# JHDrivesheet1.net
KiCad netlist of a schematic drawn in Altium Designer
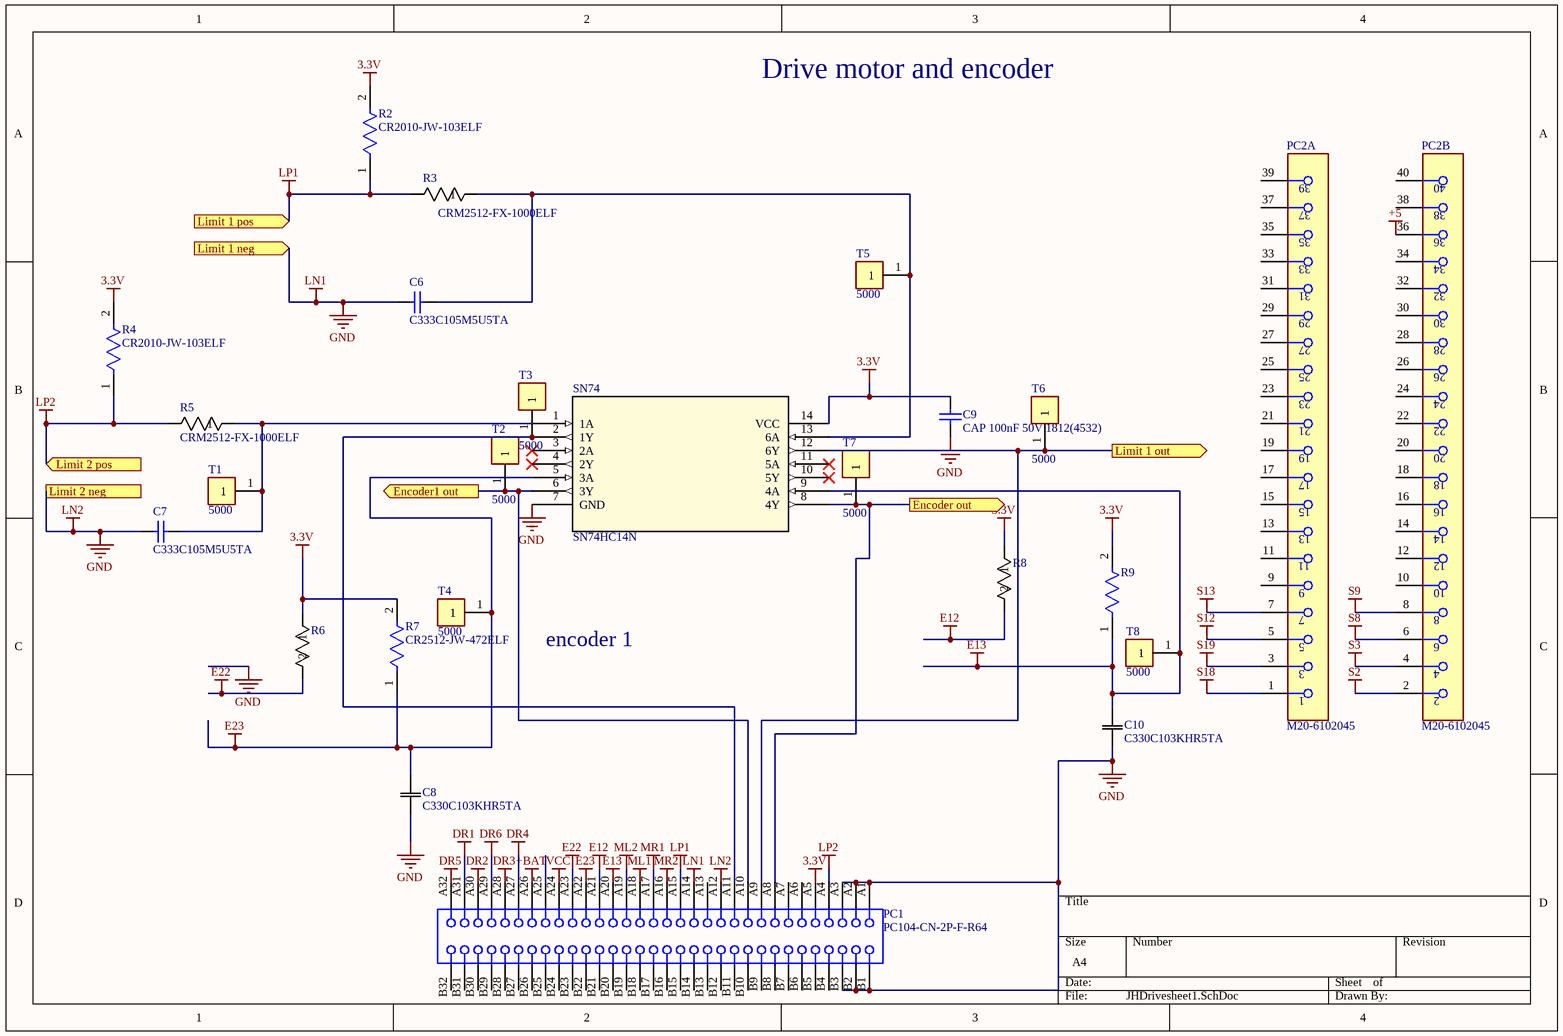
[diagram p0: JHDrivesheet1.SchDoc]

(export (version "E")
  (design (tool "Eeschema 10.0.6"))
  (components
    (comp (ref "C6")
      (value "C333C105M5U5TA")
      (footprint "KEMT-C333C105M5U5TA-2")
      (fields (field (name "MANUFACTURER") "Kemet") (field (name "TOLERANCE") "20%"))
      (libsource (lib "Altium Content Vault") (part "CAP-NP-2"))
    )
    (comp (ref "C7")
      (value "C333C105M5U5TA")
      (footprint "KEMT-C333C105M5U5TA-2")
      (fields (field (name "MANUFACTURER") "Kemet") (field (name "TOLERANCE") "20%"))
      (libsource (lib "Altium Content Vault") (part "CAP-NP-2"))
    )
    (comp (ref "C8")
      (value "C330C103KHR5TA")
      (footprint "C330C103KHR5TA:CAP_C330C_MR_COG_KEM")
      (description "No Description Available")
      (fields (field (name "COPYRIGHT") "Copyright (C) 2023 Ultra Librarian. All rights reserved."))
      (libsource (lib "C330C103KHR5TA") (part "C330C103KHR5TA"))
    )
    (comp (ref "C9")
      (value "CAP 100nF 50V 1812(4532)")
      (footprint "CAPC1812(4532)100_M")
      (description "CAP 100nF 50V ±20% 1812 (4532 Metric) Thickness 1mm SMD")
      (fields (field (name "TOLERANCE") "Â±20%"))
      (libsource (lib "Altium Content Vault") (part "CAP"))
    )
    (comp (ref "C10")
      (value "C330C103KHR5TA")
      (footprint "C330C103KHR5TA:CAP_C330C_MR_COG_KEM")
      (description "No Description Available")
      (fields (field (name "COPYRIGHT") "Copyright (C) 2023 Ultra Librarian. All rights reserved."))
      (libsource (lib "C330C103KHR5TA") (part "C330C103KHR5TA"))
    )
    (comp (ref "PC1")
      (value "PC104-CN-2P-F-R64")
      (footprint "BTB2-54-V64F-04")
      (fields (field (name "PUBLISHER") "Altium"))
      (libsource (lib "Altium Content Vault") (part "PC104-CN-2P-F-R64"))
    )
    (comp (ref "PC2")
      (value "M20-6102045")
      (footprint "FP-M20-6102045-MFG")
      (description "CONN STKTHRU PC/104 40POS PCB")
      (libsource (lib "Altium Content Vault") (part "7acf1c4a8db21028d11741a46a6ec78"))
    )
    (comp (ref "R2")
      (value "CR2010-JW-103ELF")
      (footprint "FP-CR2010-IPC_C")
      (description "Thick Film Chip Resistors 2010 10kΩ 0.5W 5% 200ppm/°C")
      (fields (field (name "TOLERANCE") "5%"))
      (libsource (lib "Altium Content Vault") (part "1029c3af85768c4190bb7ad29bc67b5"))
    )
    (comp (ref "R3")
      (value "CRM2512-FX-1000ELF")
      (footprint "BO_CR2512")
      (description "No Description Available")
      (fields (field (name "COPYRIGHT") "Copyright (C) 2023 Ultra Librarian. All rights reserved."))
      (libsource (lib "CRM2512-FX-1000ELF") (part "CRM2512-FX-1000ELF"))
    )
    (comp (ref "R4")
      (value "CR2010-JW-103ELF")
      (footprint "FP-CR2010-IPC_C")
      (description "Thick Film Chip Resistors 2010 10kΩ 0.5W 5% 200ppm/°C")
      (fields (field (name "TOLERANCE") "5%"))
      (libsource (lib "Altium Content Vault") (part "1029c3af85768c4190bb7ad29bc67b5"))
    )
    (comp (ref "R5")
      (value "CRM2512-FX-1000ELF")
      (footprint "BO_CR2512")
      (description "No Description Available")
      (fields (field (name "COPYRIGHT") "Copyright (C) 2023 Ultra Librarian. All rights reserved."))
      (libsource (lib "CRM2512-FX-1000ELF") (part "CRM2512-FX-1000ELF"))
    )
    (comp (ref "R6")
      (value "CRM2512-FX-1000ELF")
      (footprint "BO_CR2512")
      (description "No Description Available")
      (fields (field (name "COPYRIGHT") "Copyright (C) 2023 Ultra Librarian. All rights reserved."))
      (libsource (lib "CRM2512-FX-1000ELF") (part "CRM2512-FX-1000ELF"))
    )
    (comp (ref "R7")
      (value "CR2512-JW-472ELF")
      (footprint "FP-CR2512-IPC_A")
      (description "Thick Film Chip Resistors 2512 4.7kΩ 1W 5% 200ppm/°C")
      (fields (field (name "TOLERANCE") "5%"))
      (libsource (lib "Altium Content Vault") (part "1029c3af85768c4190bb7ad29bc67b5"))
    )
    (comp (ref "R8")
      (value "CRM2512-FX-1000ELF")
      (footprint "BO_CR2512")
      (description "No Description Available")
      (fields (field (name "COPYRIGHT") "Copyright (C) 2023 Ultra Librarian. All rights reserved."))
      (libsource (lib "CRM2512-FX-1000ELF") (part "CRM2512-FX-1000ELF"))
    )
    (comp (ref "R9")
      (value "CR2512-JW-472ELF")
      (footprint "FP-CR2512-IPC_A")
      (description "Thick Film Chip Resistors 2512 4.7kΩ 1W 5% 200ppm/°C")
      (fields (field (name "TOLERANCE") "5%"))
      (libsource (lib "Altium Content Vault") (part "1029c3af85768c4190bb7ad29bc67b5"))
    )
    (comp (ref "SN74")
      (value "SN74HC14N")
      (footprint "SN74HC14N:N14")
      (description "No Description Available")
      (fields (field (name "COPYRIGHT") "Copyright (C) 2023 Ultra Librarian. All rights reserved."))
      (libsource (lib "SN74HC14N") (part "SN74HC14N"))
    )
    (comp (ref "T1")
      (value "5000")
      (footprint "FP-5000-MFG")
      (description "PC TEST POINT MINIATURE RED")
      (libsource (lib "Altium Content Vault") (part "1e4615820a309e3ce90f9e6d957b7fa"))
    )
    (comp (ref "T2")
      (value "5000")
      (footprint "FP-5000-MFG")
      (description "PC TEST POINT MINIATURE RED")
      (libsource (lib "") (part "1e4615820a309e3ce90f9e6d957b7fa_1"))
    )
    (comp (ref "T3")
      (value "5000")
      (footprint "FP-5000-MFG")
      (description "PC TEST POINT MINIATURE RED")
      (libsource (lib "") (part "1e4615820a309e3ce90f9e6d957b7fa_1"))
    )
    (comp (ref "T4")
      (value "5000")
      (footprint "FP-5000-MFG")
      (description "PC TEST POINT MINIATURE RED")
      (libsource (lib "Altium Content Vault") (part "1e4615820a309e3ce90f9e6d957b7fa"))
    )
    (comp (ref "T5")
      (value "5000")
      (footprint "FP-5000-MFG")
      (description "PC TEST POINT MINIATURE RED")
      (libsource (lib "Altium Content Vault") (part "1e4615820a309e3ce90f9e6d957b7fa"))
    )
    (comp (ref "T6")
      (value "5000")
      (footprint "FP-5000-MFG")
      (description "PC TEST POINT MINIATURE RED")
      (libsource (lib "") (part "1e4615820a309e3ce90f9e6d957b7fa_1"))
    )
    (comp (ref "T7")
      (value "5000")
      (footprint "FP-5000-MFG")
      (description "PC TEST POINT MINIATURE RED")
      (libsource (lib "") (part "1e4615820a309e3ce90f9e6d957b7fa_1"))
    )
    (comp (ref "T8")
      (value "5000")
      (footprint "FP-5000-MFG")
      (description "PC TEST POINT MINIATURE RED")
      (libsource (lib "Altium Content Vault") (part "1e4615820a309e3ce90f9e6d957b7fa"))
    )
  )
  (nets
    (net (code "1") (name "+5") (class "Default")
      (node (ref "PC2") (pin "36") (pinfunction "36_36") (pintype "passive"))
    )
    (net (code "2") (name "+BAT") (class "Default")
      (node (ref "PC1") (pin "A26") (pinfunction "26_A26") (pintype "passive"))
    )
    (net (code "3") (name "/Encoder out") (class "Default")
      (node (ref "PC1") (pin "A8") (pinfunction "8_A8") (pintype "passive"))
      (node (ref "SN74") (pin "8") (pinfunction "4Y_8") (pintype "output"))
      (node (ref "T7") (pin "1") (pinfunction "1_1") (pintype "passive"))
    )
    (net (code "4") (name "/Encoder1 out") (class "Default")
      (node (ref "PC1") (pin "A10") (pinfunction "10_A10") (pintype "passive"))
      (node (ref "SN74") (pin "6") (pinfunction "3Y_6") (pintype "output"))
      (node (ref "T2") (pin "1") (pinfunction "1_1") (pintype "passive"))
    )
    (net (code "5") (name "/Limit 1 out") (class "Default")
      (node (ref "PC1") (pin "A9") (pinfunction "9_A9") (pintype "passive"))
      (node (ref "SN74") (pin "12") (pinfunction "6Y_12") (pintype "output"))
      (node (ref "T6") (pin "1") (pinfunction "1_1") (pintype "passive"))
    )
    (net (code "6") (name "3.3V") (class "Default")
      (node (ref "C9") (pin "2") (pinfunction "2_2") (pintype "passive"))
      (node (ref "PC1") (pin "A5") (pinfunction "5_A5") (pintype "passive"))
      (node (ref "R2") (pin "2") (pinfunction "2_2") (pintype "passive"))
      (node (ref "R4") (pin "2") (pinfunction "2_2") (pintype "passive"))
      (node (ref "R6") (pin "1") (pinfunction "1_1") (pintype "passive"))
      (node (ref "R7") (pin "2") (pinfunction "2_2") (pintype "passive"))
      (node (ref "R8") (pin "1") (pinfunction "1_1") (pintype "passive"))
      (node (ref "R9") (pin "2") (pinfunction "2_2") (pintype "passive"))
      (node (ref "SN74") (pin "14") (pinfunction "VCC_14") (pintype "power_in"))
    )
    (net (code "7") (name "DR1") (class "Default")
      (node (ref "PC1") (pin "A31") (pinfunction "31_A31") (pintype "passive"))
    )
    (net (code "8") (name "DR2") (class "Default")
      (node (ref "PC1") (pin "A30") (pinfunction "30_A30") (pintype "passive"))
    )
    (net (code "9") (name "DR3") (class "Default")
      (node (ref "PC1") (pin "A28") (pinfunction "28_A28") (pintype "passive"))
    )
    (net (code "10") (name "DR4") (class "Default")
      (node (ref "PC1") (pin "A27") (pinfunction "27_A27") (pintype "passive"))
    )
    (net (code "11") (name "DR5") (class "Default")
      (node (ref "PC1") (pin "A32") (pinfunction "32_A32") (pintype "passive"))
    )
    (net (code "12") (name "DR6") (class "Default")
      (node (ref "PC1") (pin "A29") (pinfunction "29_A29") (pintype "passive"))
    )
    (net (code "13") (name "E12") (class "Default")
      (node (ref "PC1") (pin "A21") (pinfunction "21_A21") (pintype "passive"))
      (node (ref "R8") (pin "2") (pinfunction "2_2") (pintype "passive"))
    )
    (net (code "14") (name "E13") (class "Default")
      (node (ref "C10") (pin "2") (pinfunction "2_2") (pintype "passive"))
      (node (ref "PC1") (pin "A20") (pinfunction "20_A20") (pintype "passive"))
      (node (ref "R9") (pin "1") (pinfunction "1_1") (pintype "passive"))
      (node (ref "SN74") (pin "9") (pinfunction "4A_9") (pintype "input"))
      (node (ref "T8") (pin "1") (pinfunction "1_1") (pintype "passive"))
    )
    (net (code "15") (name "E22") (class "Default")
      (node (ref "PC1") (pin "A23") (pinfunction "23_A23") (pintype "passive"))
      (node (ref "R6") (pin "2") (pinfunction "2_2") (pintype "passive"))
    )
    (net (code "16") (name "E23") (class "Default")
      (node (ref "C8") (pin "2") (pinfunction "2_2") (pintype "passive"))
      (node (ref "PC1") (pin "A22") (pinfunction "22_A22") (pintype "passive"))
      (node (ref "R7") (pin "1") (pinfunction "1_1") (pintype "passive"))
      (node (ref "SN74") (pin "5") (pinfunction "3A_5") (pintype "input"))
      (node (ref "T4") (pin "1") (pinfunction "1_1") (pintype "passive"))
    )
    (net (code "17") (name "GND") (class "Default")
      (node (ref "C10") (pin "1") (pinfunction "1_1") (pintype "passive"))
      (node (ref "C6") (pin "1") (pinfunction "1_1") (pintype "passive"))
      (node (ref "C7") (pin "1") (pinfunction "1_1") (pintype "passive"))
      (node (ref "C8") (pin "1") (pinfunction "1_1") (pintype "passive"))
      (node (ref "C9") (pin "1") (pinfunction "1_1") (pintype "passive"))
      (node (ref "PC1") (pin "A1") (pinfunction "1_A1") (pintype "passive"))
      (node (ref "PC1") (pin "A12") (pinfunction "12_A12") (pintype "passive"))
      (node (ref "PC1") (pin "A14") (pinfunction "14_A14") (pintype "passive"))
      (node (ref "PC1") (pin "A2") (pinfunction "2_A2") (pintype "passive"))
      (node (ref "PC1") (pin "A3") (pinfunction "3_A3") (pintype "passive"))
      (node (ref "PC1") (pin "B1") (pinfunction "33_B1") (pintype "passive"))
      (node (ref "PC1") (pin "B2") (pinfunction "34_B2") (pintype "passive"))
      (node (ref "PC1") (pin "B3") (pinfunction "35_B3") (pintype "passive"))
      (node (ref "SN74") (pin "7") (pinfunction "GND_7") (pintype "power_in"))
    )
    (net (code "18") (name "LP1") (class "Default")
      (node (ref "PC1") (pin "A15") (pinfunction "15_A15") (pintype "passive"))
      (node (ref "R2") (pin "1") (pinfunction "1_1") (pintype "passive"))
      (node (ref "R3") (pin "2") (pinfunction "2_2") (pintype "passive"))
    )
    (net (code "19") (name "LP2") (class "Default")
      (node (ref "PC1") (pin "A4") (pinfunction "4_A4") (pintype "passive"))
      (node (ref "R4") (pin "1") (pinfunction "1_1") (pintype "passive"))
      (node (ref "R5") (pin "2") (pinfunction "2_2") (pintype "passive"))
    )
    (net (code "20") (name "ML1") (class "Default")
      (node (ref "PC1") (pin "A18") (pinfunction "18_A18") (pintype "passive"))
    )
    (net (code "21") (name "ML2") (class "Default")
      (node (ref "PC1") (pin "A19") (pinfunction "19_A19") (pintype "passive"))
    )
    (net (code "22") (name "MR1") (class "Default")
      (node (ref "PC1") (pin "A17") (pinfunction "17_A17") (pintype "passive"))
    )
    (net (code "23") (name "MR2") (class "Default")
      (node (ref "PC1") (pin "A16") (pinfunction "16_A16") (pintype "passive"))
    )
    (net (code "24") (name "Net-(PC1-11)") (class "Default")
      (node (ref "PC1") (pin "A11") (pinfunction "11_A11") (pintype "passive"))
      (node (ref "SN74") (pin "2") (pinfunction "1Y_2") (pintype "output"))
      (node (ref "T3") (pin "1") (pinfunction "1_1") (pintype "passive"))
    )
    (net (code "25") (name "Net-(SN74-1A)") (class "Default")
      (node (ref "C7") (pin "2") (pinfunction "2_2") (pintype "passive"))
      (node (ref "R5") (pin "1") (pinfunction "1_1") (pintype "passive"))
      (node (ref "SN74") (pin "1") (pinfunction "1A_1") (pintype "input"))
      (node (ref "T1") (pin "1") (pinfunction "1_1") (pintype "passive"))
    )
    (net (code "26") (name "Net-(SN74-6A)") (class "Default")
      (node (ref "C6") (pin "2") (pinfunction "2_2") (pintype "passive"))
      (node (ref "R3") (pin "1") (pinfunction "1_1") (pintype "passive"))
      (node (ref "SN74") (pin "13") (pinfunction "6A_13") (pintype "input"))
      (node (ref "T5") (pin "1") (pinfunction "1_1") (pintype "passive"))
    )
    (net (code "27") (name "S2") (class "Default")
      (node (ref "PC2") (pin "2") (pinfunction "2_2") (pintype "passive"))
    )
    (net (code "28") (name "S3") (class "Default")
      (node (ref "PC2") (pin "4") (pinfunction "4_4") (pintype "passive"))
    )
    (net (code "29") (name "S8") (class "Default")
      (node (ref "PC2") (pin "6") (pinfunction "6_6") (pintype "passive"))
    )
    (net (code "30") (name "S9") (class "Default")
      (node (ref "PC2") (pin "8") (pinfunction "8_8") (pintype "passive"))
    )
    (net (code "31") (name "S12") (class "Default")
      (node (ref "PC2") (pin "5") (pinfunction "5_5") (pintype "passive"))
    )
    (net (code "32") (name "S13") (class "Default")
      (node (ref "PC2") (pin "7") (pinfunction "7_7") (pintype "passive"))
    )
    (net (code "33") (name "S18") (class "Default")
      (node (ref "PC2") (pin "1") (pinfunction "1_1") (pintype "passive"))
    )
    (net (code "34") (name "S19") (class "Default")
      (node (ref "PC2") (pin "3") (pinfunction "3_3") (pintype "passive"))
    )
    (net (code "35") (name "VCC") (class "Default")
      (node (ref "PC1") (pin "A24") (pinfunction "24_A24") (pintype "passive"))
    )
    (net (code "36") (name "unconnected-(PC1-6-PadA6)") (class "Default")
      (node (ref "PC1") (pin "A6") (pinfunction "6_A6") (pintype "passive"))
    )
    (net (code "37") (name "unconnected-(PC1-7-PadA7)") (class "Default")
      (node (ref "PC1") (pin "A7") (pinfunction "7_A7") (pintype "passive"))
    )
    (net (code "38") (name "unconnected-(PC1-13-PadA13)") (class "Default")
      (node (ref "PC1") (pin "A13") (pinfunction "13_A13") (pintype "passive"))
    )
    (net (code "39") (name "unconnected-(PC1-25-PadA25)") (class "Default")
      (node (ref "PC1") (pin "A25") (pinfunction "25_A25") (pintype "passive"))
    )
    (net (code "40") (name "unconnected-(PC1-36-PadB4)") (class "Default")
      (node (ref "PC1") (pin "B4") (pinfunction "36_B4") (pintype "passive"))
    )
    (net (code "41") (name "unconnected-(PC1-37-PadB5)") (class "Default")
      (node (ref "PC1") (pin "B5") (pinfunction "37_B5") (pintype "passive"))
    )
    (net (code "42") (name "unconnected-(PC1-38-PadB6)") (class "Default")
      (node (ref "PC1") (pin "B6") (pinfunction "38_B6") (pintype "passive"))
    )
    (net (code "43") (name "unconnected-(PC1-39-PadB7)") (class "Default")
      (node (ref "PC1") (pin "B7") (pinfunction "39_B7") (pintype "passive"))
    )
    (net (code "44") (name "unconnected-(PC1-40-PadB8)") (class "Default")
      (node (ref "PC1") (pin "B8") (pinfunction "40_B8") (pintype "passive"))
    )
    (net (code "45") (name "unconnected-(PC1-41-PadB9)") (class "Default")
      (node (ref "PC1") (pin "B9") (pinfunction "41_B9") (pintype "passive"))
    )
    (net (code "46") (name "unconnected-(PC1-42-PadB10)") (class "Default")
      (node (ref "PC1") (pin "B10") (pinfunction "42_B10") (pintype "passive"))
    )
    (net (code "47") (name "unconnected-(PC1-43-PadB11)") (class "Default")
      (node (ref "PC1") (pin "B11") (pinfunction "43_B11") (pintype "passive"))
    )
    (net (code "48") (name "unconnected-(PC1-44-PadB12)") (class "Default")
      (node (ref "PC1") (pin "B12") (pinfunction "44_B12") (pintype "passive"))
    )
    (net (code "49") (name "unconnected-(PC1-45-PadB13)") (class "Default")
      (node (ref "PC1") (pin "B13") (pinfunction "45_B13") (pintype "passive"))
    )
    (net (code "50") (name "unconnected-(PC1-46-PadB14)") (class "Default")
      (node (ref "PC1") (pin "B14") (pinfunction "46_B14") (pintype "passive"))
    )
    (net (code "51") (name "unconnected-(PC1-47-PadB15)") (class "Default")
      (node (ref "PC1") (pin "B15") (pinfunction "47_B15") (pintype "passive"))
    )
    (net (code "52") (name "unconnected-(PC1-48-PadB16)") (class "Default")
      (node (ref "PC1") (pin "B16") (pinfunction "48_B16") (pintype "passive"))
    )
    (net (code "53") (name "unconnected-(PC1-49-PadB17)") (class "Default")
      (node (ref "PC1") (pin "B17") (pinfunction "49_B17") (pintype "passive"))
    )
    (net (code "54") (name "unconnected-(PC1-50-PadB18)") (class "Default")
      (node (ref "PC1") (pin "B18") (pinfunction "50_B18") (pintype "passive"))
    )
    (net (code "55") (name "unconnected-(PC1-51-PadB19)") (class "Default")
      (node (ref "PC1") (pin "B19") (pinfunction "51_B19") (pintype "passive"))
    )
    (net (code "56") (name "unconnected-(PC1-52-PadB20)") (class "Default")
      (node (ref "PC1") (pin "B20") (pinfunction "52_B20") (pintype "passive"))
    )
    (net (code "57") (name "unconnected-(PC1-53-PadB21)") (class "Default")
      (node (ref "PC1") (pin "B21") (pinfunction "53_B21") (pintype "passive"))
    )
    (net (code "58") (name "unconnected-(PC1-54-PadB22)") (class "Default")
      (node (ref "PC1") (pin "B22") (pinfunction "54_B22") (pintype "passive"))
    )
    (net (code "59") (name "unconnected-(PC1-55-PadB23)") (class "Default")
      (node (ref "PC1") (pin "B23") (pinfunction "55_B23") (pintype "passive"))
    )
    (net (code "60") (name "unconnected-(PC1-56-PadB24)") (class "Default")
      (node (ref "PC1") (pin "B24") (pinfunction "56_B24") (pintype "passive"))
    )
    (net (code "61") (name "unconnected-(PC1-57-PadB25)") (class "Default")
      (node (ref "PC1") (pin "B25") (pinfunction "57_B25") (pintype "passive"))
    )
    (net (code "62") (name "unconnected-(PC1-58-PadB26)") (class "Default")
      (node (ref "PC1") (pin "B26") (pinfunction "58_B26") (pintype "passive"))
    )
    (net (code "63") (name "unconnected-(PC1-59-PadB27)") (class "Default")
      (node (ref "PC1") (pin "B27") (pinfunction "59_B27") (pintype "passive"))
    )
    (net (code "64") (name "unconnected-(PC1-60-PadB28)") (class "Default")
      (node (ref "PC1") (pin "B28") (pinfunction "60_B28") (pintype "passive"))
    )
    (net (code "65") (name "unconnected-(PC1-61-PadB29)") (class "Default")
      (node (ref "PC1") (pin "B29") (pinfunction "61_B29") (pintype "passive"))
    )
    (net (code "66") (name "unconnected-(PC1-62-PadB30)") (class "Default")
      (node (ref "PC1") (pin "B30") (pinfunction "62_B30") (pintype "passive"))
    )
    (net (code "67") (name "unconnected-(PC1-63-PadB31)") (class "Default")
      (node (ref "PC1") (pin "B31") (pinfunction "63_B31") (pintype "passive"))
    )
    (net (code "68") (name "unconnected-(PC1-64-PadB32)") (class "Default")
      (node (ref "PC1") (pin "B32") (pinfunction "64_B32") (pintype "passive"))
    )
    (net (code "69") (name "unconnected-(PC2-Pad9)") (class "Default")
      (node (ref "PC2") (pin "9") (pinfunction "9_9") (pintype "passive"))
    )
    (net (code "70") (name "unconnected-(PC2-Pad10)") (class "Default")
      (node (ref "PC2") (pin "10") (pinfunction "10_10") (pintype "passive"))
    )
    (net (code "71") (name "unconnected-(PC2-Pad11)") (class "Default")
      (node (ref "PC2") (pin "11") (pinfunction "11_11") (pintype "passive"))
    )
    (net (code "72") (name "unconnected-(PC2-Pad12)") (class "Default")
      (node (ref "PC2") (pin "12") (pinfunction "12_12") (pintype "passive"))
    )
    (net (code "73") (name "unconnected-(PC2-Pad13)") (class "Default")
      (node (ref "PC2") (pin "13") (pinfunction "13_13") (pintype "passive"))
    )
    (net (code "74") (name "unconnected-(PC2-Pad14)") (class "Default")
      (node (ref "PC2") (pin "14") (pinfunction "14_14") (pintype "passive"))
    )
    (net (code "75") (name "unconnected-(PC2-Pad15)") (class "Default")
      (node (ref "PC2") (pin "15") (pinfunction "15_15") (pintype "passive"))
    )
    (net (code "76") (name "unconnected-(PC2-Pad16)") (class "Default")
      (node (ref "PC2") (pin "16") (pinfunction "16_16") (pintype "passive"))
    )
    (net (code "77") (name "unconnected-(PC2-Pad17)") (class "Default")
      (node (ref "PC2") (pin "17") (pinfunction "17_17") (pintype "passive"))
    )
    (net (code "78") (name "unconnected-(PC2-Pad18)") (class "Default")
      (node (ref "PC2") (pin "18") (pinfunction "18_18") (pintype "passive"))
    )
    (net (code "79") (name "unconnected-(PC2-Pad19)") (class "Default")
      (node (ref "PC2") (pin "19") (pinfunction "19_19") (pintype "passive"))
    )
    (net (code "80") (name "unconnected-(PC2-Pad20)") (class "Default")
      (node (ref "PC2") (pin "20") (pinfunction "20_20") (pintype "passive"))
    )
    (net (code "81") (name "unconnected-(PC2-Pad21)") (class "Default")
      (node (ref "PC2") (pin "21") (pinfunction "21_21") (pintype "passive"))
    )
    (net (code "82") (name "unconnected-(PC2-Pad22)") (class "Default")
      (node (ref "PC2") (pin "22") (pinfunction "22_22") (pintype "passive"))
    )
    (net (code "83") (name "unconnected-(PC2-Pad23)") (class "Default")
      (node (ref "PC2") (pin "23") (pinfunction "23_23") (pintype "passive"))
    )
    (net (code "84") (name "unconnected-(PC2-Pad24)") (class "Default")
      (node (ref "PC2") (pin "24") (pinfunction "24_24") (pintype "passive"))
    )
    (net (code "85") (name "unconnected-(PC2-Pad25)") (class "Default")
      (node (ref "PC2") (pin "25") (pinfunction "25_25") (pintype "passive"))
    )
    (net (code "86") (name "unconnected-(PC2-Pad26)") (class "Default")
      (node (ref "PC2") (pin "26") (pinfunction "26_26") (pintype "passive"))
    )
    (net (code "87") (name "unconnected-(PC2-Pad27)") (class "Default")
      (node (ref "PC2") (pin "27") (pinfunction "27_27") (pintype "passive"))
    )
    (net (code "88") (name "unconnected-(PC2-Pad28)") (class "Default")
      (node (ref "PC2") (pin "28") (pinfunction "28_28") (pintype "passive"))
    )
    (net (code "89") (name "unconnected-(PC2-Pad29)") (class "Default")
      (node (ref "PC2") (pin "29") (pinfunction "29_29") (pintype "passive"))
    )
    (net (code "90") (name "unconnected-(PC2-Pad30)") (class "Default")
      (node (ref "PC2") (pin "30") (pinfunction "30_30") (pintype "passive"))
    )
    (net (code "91") (name "unconnected-(PC2-Pad31)") (class "Default")
      (node (ref "PC2") (pin "31") (pinfunction "31_31") (pintype "passive"))
    )
    (net (code "92") (name "unconnected-(PC2-Pad32)") (class "Default")
      (node (ref "PC2") (pin "32") (pinfunction "32_32") (pintype "passive"))
    )
    (net (code "93") (name "unconnected-(PC2-Pad33)") (class "Default")
      (node (ref "PC2") (pin "33") (pinfunction "33_33") (pintype "passive"))
    )
    (net (code "94") (name "unconnected-(PC2-Pad34)") (class "Default")
      (node (ref "PC2") (pin "34") (pinfunction "34_34") (pintype "passive"))
    )
    (net (code "95") (name "unconnected-(PC2-Pad35)") (class "Default")
      (node (ref "PC2") (pin "35") (pinfunction "35_35") (pintype "passive"))
    )
    (net (code "96") (name "unconnected-(PC2-Pad37)") (class "Default")
      (node (ref "PC2") (pin "37") (pinfunction "37_37") (pintype "passive"))
    )
    (net (code "97") (name "unconnected-(PC2-Pad38)") (class "Default")
      (node (ref "PC2") (pin "38") (pinfunction "38_38") (pintype "passive"))
    )
    (net (code "98") (name "unconnected-(PC2-Pad39)") (class "Default")
      (node (ref "PC2") (pin "39") (pinfunction "39_39") (pintype "passive"))
    )
    (net (code "99") (name "unconnected-(PC2-Pad40)") (class "Default")
      (node (ref "PC2") (pin "40") (pinfunction "40_40") (pintype "passive"))
    )
    (net (code "100") (name "unconnected-(SN74-2A-Pad3)") (class "Default")
      (node (ref "SN74") (pin "3") (pinfunction "2A_3") (pintype "input+no_connect"))
    )
    (net (code "101") (name "unconnected-(SN74-2Y-Pad4)") (class "Default")
      (node (ref "SN74") (pin "4") (pinfunction "2Y_4") (pintype "output+no_connect"))
    )
    (net (code "102") (name "unconnected-(SN74-5A-Pad11)") (class "Default")
      (node (ref "SN74") (pin "11") (pinfunction "5A_11") (pintype "input+no_connect"))
    )
    (net (code "103") (name "unconnected-(SN74-5Y-Pad10)") (class "Default")
      (node (ref "SN74") (pin "10") (pinfunction "5Y_10") (pintype "output+no_connect"))
    )
  )
)
